# ProPrj_SCH_1_69_v2_2024-10-31_2024-11-01.net
KiCad netlist of a schematic drawn in EasyEDA Pro
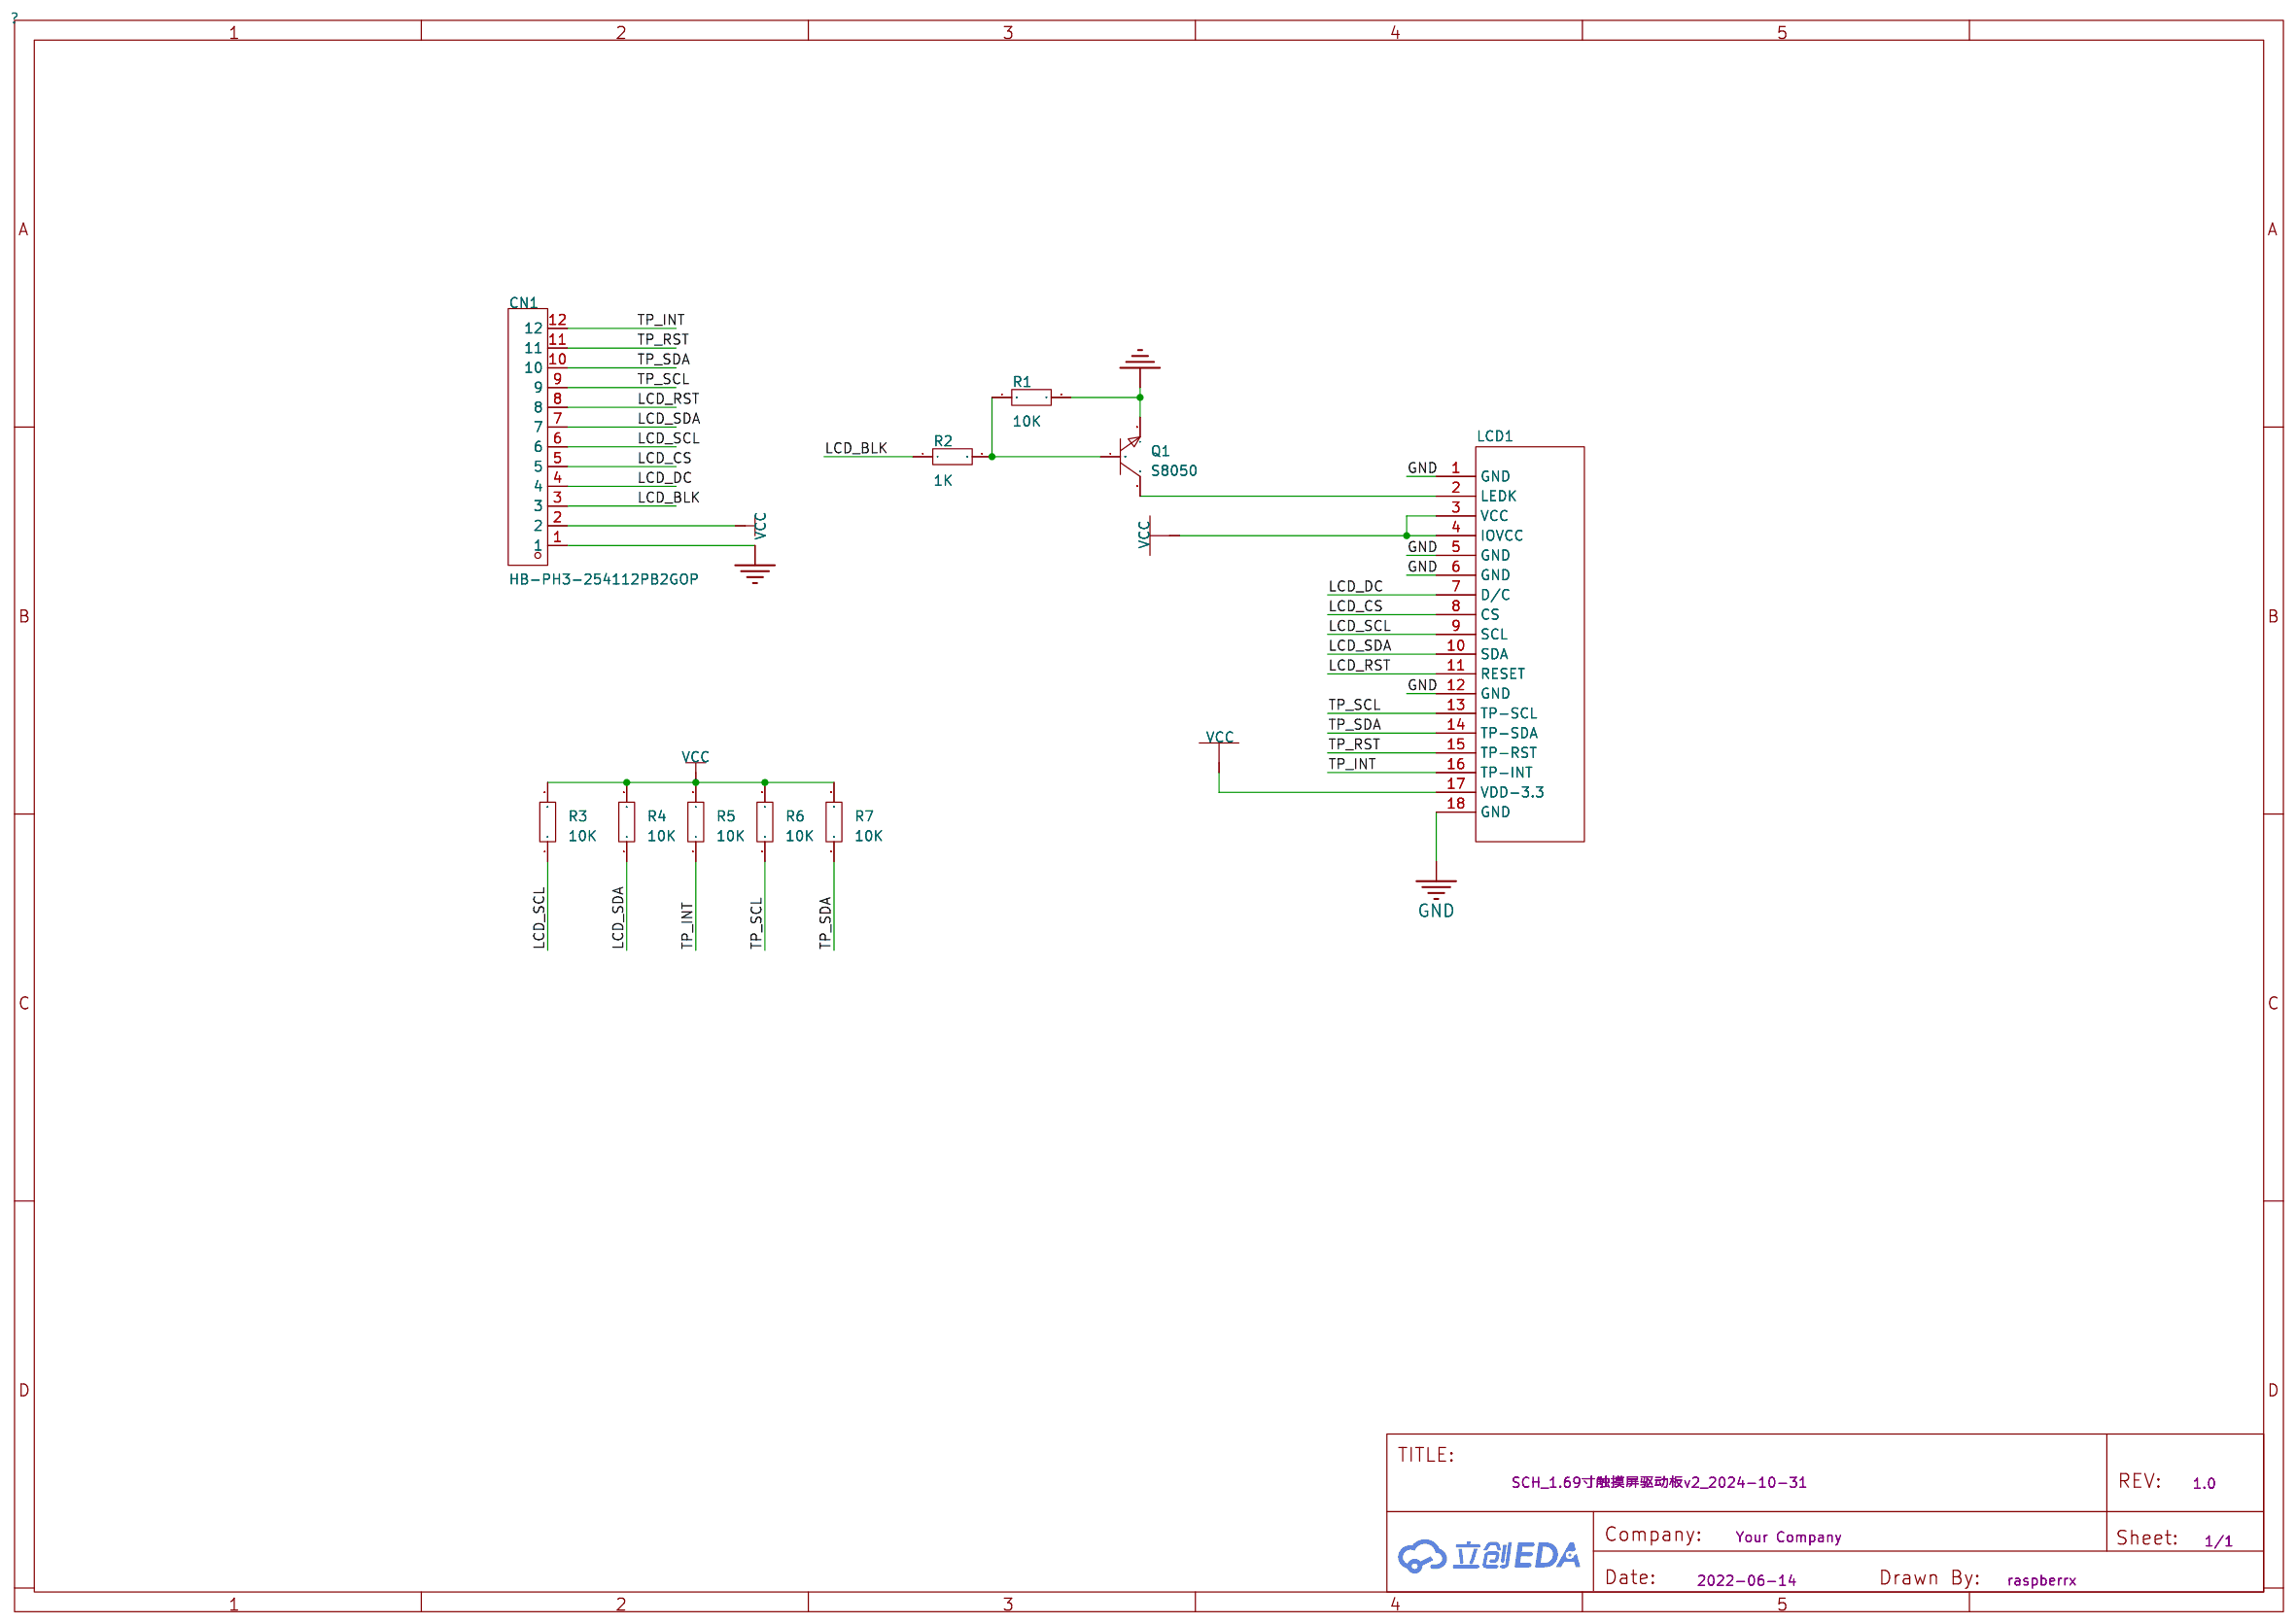
[diagram p0: schematic sheet]

(export (version "E")
  (design (tool "Eeschema 10.0.6"))
  (components
    (comp (ref "CN1")
      (value "HB-PH3-254112PB2GOP")
      (footprint "easyedapro:HDR-TH_12P-P2.54-V-M")
      (fields (field (name "Manufacturer") "HANBO(汉博)"))
      (libsource (lib "easyedapro") (part "HB-PH3-254112PB2GOP"))
    )
    (comp (ref "LCD1")
      (value "~")
      (footprint "easyedapro:FPC-SMD_18P-P0.50_HDGC_0.5K-HX-18PWB")
      (description "https://item.taobao.com/item.htm?spm=a1z0d.6639537.1997196601.49.7a0174846ueIFD&id=662619384744")
      (libsource (lib "easyedapro") (part "淘宝1.69寸屏幕"))
    )
    (comp (ref "Q1")
      (value "S8050")
      (footprint "easyedapro:SOT-23-3_L2.9-W1.3-P1.90-LS2.3-BR")
      (description "晶体管类型:NPN;集电极电流(Ic):500mA;集射极击穿电压(Vceo):25V;功率(Pd):300mW;直流电流增益(hFE@Ic,Vce):120@50mA,1.0V;")
      (fields (field (name "Manufacturer") "宏迦橙"))
      (libsource (lib "easyedapro") (part "s8050_c20069125"))
    )
    (comp (ref "R1") (value "10K") (footprint "easyedapro:R0603") (libsource (lib "easyedapro") (part "电阻")))
    (comp (ref "R2") (value "1K") (footprint "easyedapro:R0603") (libsource (lib "easyedapro") (part "电阻")))
    (comp (ref "R3") (value "10K") (footprint "easyedapro:R0603") (libsource (lib "easyedapro") (part "电阻")))
    (comp (ref "R4") (value "10K") (footprint "easyedapro:R0603") (libsource (lib "easyedapro") (part "电阻")))
    (comp (ref "R5") (value "10K") (footprint "easyedapro:R0603") (libsource (lib "easyedapro") (part "电阻")))
    (comp (ref "R6") (value "10K") (footprint "easyedapro:R0603") (libsource (lib "easyedapro") (part "电阻")))
    (comp (ref "R7") (value "10K") (footprint "easyedapro:R0603") (libsource (lib "easyedapro") (part "电阻")))
  )
  (nets
    (net (code "1") (name "/LCD_BLK") (class "Default")
      (node (ref "CN1") (pin "3") (pinfunction "3_3") (pintype "unspecified"))
      (node (ref "R2") (pin "1") (pinfunction "1_1") (pintype "input"))
    )
    (net (code "2") (name "/LCD_CS") (class "Default")
      (node (ref "CN1") (pin "5") (pinfunction "5_5") (pintype "unspecified"))
      (node (ref "LCD1") (pin "8") (pinfunction "CS_8") (pintype "input"))
    )
    (net (code "3") (name "/LCD_DC") (class "Default")
      (node (ref "CN1") (pin "4") (pinfunction "4_4") (pintype "unspecified"))
      (node (ref "LCD1") (pin "7") (pinfunction "D/C_7") (pintype "input"))
    )
    (net (code "4") (name "/LCD_RST") (class "Default")
      (node (ref "CN1") (pin "8") (pinfunction "8_8") (pintype "unspecified"))
      (node (ref "LCD1") (pin "11") (pinfunction "RESET_11") (pintype "input"))
    )
    (net (code "5") (name "/LCD_SCL") (class "Default")
      (node (ref "CN1") (pin "6") (pinfunction "6_6") (pintype "unspecified"))
      (node (ref "LCD1") (pin "9") (pinfunction "SCL_9") (pintype "input"))
      (node (ref "R3") (pin "1") (pinfunction "1_1") (pintype "input"))
    )
    (net (code "6") (name "/LCD_SDA") (class "Default")
      (node (ref "CN1") (pin "7") (pinfunction "7_7") (pintype "unspecified"))
      (node (ref "LCD1") (pin "10") (pinfunction "SDA_10") (pintype "input"))
      (node (ref "R4") (pin "1") (pinfunction "1_1") (pintype "input"))
    )
    (net (code "7") (name "/TP_INT") (class "Default")
      (node (ref "CN1") (pin "12") (pinfunction "12_12") (pintype "unspecified"))
      (node (ref "LCD1") (pin "16") (pinfunction "TP-INT_16") (pintype "input"))
      (node (ref "R5") (pin "1") (pinfunction "1_1") (pintype "input"))
    )
    (net (code "8") (name "/TP_RST") (class "Default")
      (node (ref "CN1") (pin "11") (pinfunction "11_11") (pintype "unspecified"))
      (node (ref "LCD1") (pin "15") (pinfunction "TP-RST_15") (pintype "input"))
    )
    (net (code "9") (name "/TP_SCL") (class "Default")
      (node (ref "CN1") (pin "9") (pinfunction "9_9") (pintype "unspecified"))
      (node (ref "LCD1") (pin "13") (pinfunction "TP-SCL_13") (pintype "input"))
      (node (ref "R6") (pin "1") (pinfunction "1_1") (pintype "input"))
    )
    (net (code "10") (name "/TP_SDA") (class "Default")
      (node (ref "CN1") (pin "10") (pinfunction "10_10") (pintype "unspecified"))
      (node (ref "LCD1") (pin "14") (pinfunction "TP-SDA_14") (pintype "input"))
      (node (ref "R7") (pin "1") (pinfunction "1_1") (pintype "input"))
    )
    (net (code "11") (name "GND") (class "Default")
      (node (ref "CN1") (pin "1") (pinfunction "1_1") (pintype "unspecified"))
      (node (ref "LCD1") (pin "1") (pinfunction "GND_1") (pintype "input"))
      (node (ref "LCD1") (pin "12") (pinfunction "GND_12") (pintype "input"))
      (node (ref "LCD1") (pin "18") (pinfunction "GND_18") (pintype "input"))
      (node (ref "LCD1") (pin "5") (pinfunction "GND_5") (pintype "input"))
      (node (ref "LCD1") (pin "6") (pinfunction "GND_6") (pintype "input"))
      (node (ref "Q1") (pin "2") (pinfunction "E_2") (pintype "input"))
      (node (ref "R1") (pin "2") (pinfunction "2_2") (pintype "input"))
    )
    (net (code "12") (name "Net-(LCD1-LEDK)") (class "Default")
      (node (ref "LCD1") (pin "2") (pinfunction "LEDK_2") (pintype "input"))
      (node (ref "Q1") (pin "3") (pinfunction "C_3") (pintype "input"))
    )
    (net (code "13") (name "Net-(Q1-B)") (class "Default")
      (node (ref "Q1") (pin "1") (pinfunction "B_1") (pintype "input"))
      (node (ref "R1") (pin "1") (pinfunction "1_1") (pintype "input"))
      (node (ref "R2") (pin "2") (pinfunction "2_2") (pintype "input"))
    )
    (net (code "14") (name "VCC") (class "Default")
      (node (ref "CN1") (pin "2") (pinfunction "2_2") (pintype "unspecified"))
      (node (ref "LCD1") (pin "17") (pinfunction "VDD-3.3_17") (pintype "input"))
      (node (ref "LCD1") (pin "3") (pinfunction "VCC_3") (pintype "input"))
      (node (ref "LCD1") (pin "4") (pinfunction "IOVCC_4") (pintype "input"))
      (node (ref "R3") (pin "2") (pinfunction "2_2") (pintype "input"))
      (node (ref "R4") (pin "2") (pinfunction "2_2") (pintype "input"))
      (node (ref "R5") (pin "2") (pinfunction "2_2") (pintype "input"))
      (node (ref "R6") (pin "2") (pinfunction "2_2") (pintype "input"))
      (node (ref "R7") (pin "2") (pinfunction "2_2") (pintype "input"))
    )
  )
)
